# PICZone.net
KiCad netlist of a schematic drawn in Altium Designer
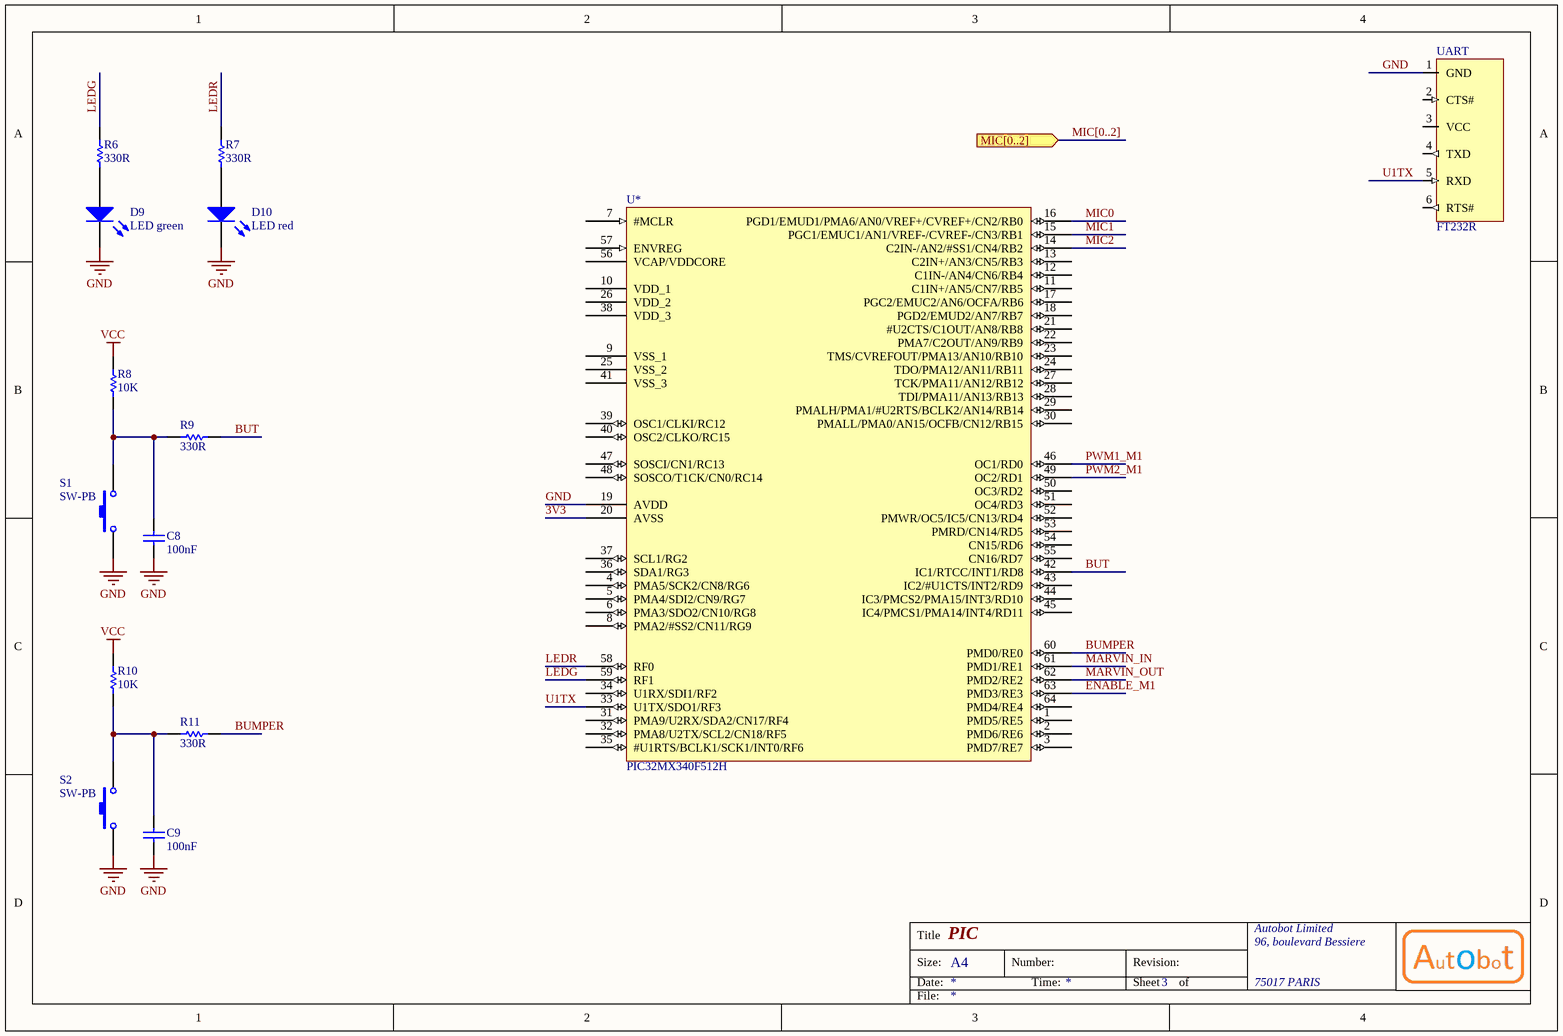
[diagram p0: PICZone.SchDoc]

(export (version "E")
  (design (tool "Eeschema 10.0.6"))
  (components
    (comp (ref "C8")
      (value "100nF")
      (footprint "RAD-0.3")
      (description "Capacitor")
      (fields (field (name "PUBLISHER") "Altium Limited"))
      (libsource (lib "Miscellaneous Devices") (part "Cap"))
    )
    (comp (ref "C9")
      (value "100nF")
      (footprint "RAD-0.3")
      (description "Capacitor")
      (fields (field (name "PUBLISHER") "Altium Limited"))
      (libsource (lib "Miscellaneous Devices") (part "Cap"))
    )
    (comp (ref "D9")
      (value "LED green")
      (footprint "LED-0")
      (description "Typical INFRARED GaAs LED")
      (fields (field (name "PUBLISHER") "Altium Limited"))
      (libsource (lib "Miscellaneous Devices") (part "LED0"))
    )
    (comp (ref "D10")
      (value "LED red")
      (footprint "LED-0")
      (description "Typical INFRARED GaAs LED")
      (fields (field (name "PUBLISHER") "Altium Limited"))
      (libsource (lib "Miscellaneous Devices") (part "LED0"))
    )
    (comp (ref "R6")
      (value "330R")
      (footprint "AXIAL-0.3")
      (description "Resistor")
      (fields (field (name "PUBLISHER") "Altium Limited"))
      (libsource (lib "Miscellaneous Devices") (part "Res1"))
    )
    (comp (ref "R7")
      (value "330R")
      (footprint "AXIAL-0.3")
      (description "Resistor")
      (fields (field (name "PUBLISHER") "Altium Limited"))
      (libsource (lib "Miscellaneous Devices") (part "Res1"))
    )
    (comp (ref "R8")
      (value "10K")
      (footprint "AXIAL-0.3")
      (description "Resistor")
      (fields (field (name "PUBLISHER") "Altium Limited"))
      (libsource (lib "Miscellaneous Devices") (part "Res1"))
    )
    (comp (ref "R9")
      (value "330R")
      (footprint "AXIAL-0.3")
      (description "Resistor")
      (fields (field (name "PUBLISHER") "Altium Limited"))
      (libsource (lib "Miscellaneous Devices") (part "Res1"))
    )
    (comp (ref "R10")
      (value "10K")
      (footprint "AXIAL-0.3")
      (description "Resistor")
      (fields (field (name "PUBLISHER") "Altium Limited"))
      (libsource (lib "Miscellaneous Devices") (part "Res1"))
    )
    (comp (ref "R11")
      (value "330R")
      (footprint "AXIAL-0.3")
      (description "Resistor")
      (fields (field (name "PUBLISHER") "Altium Limited"))
      (libsource (lib "Miscellaneous Devices") (part "Res1"))
    )
    (comp (ref "S1")
      (value "SW-PB")
      (footprint "SPST-2")
      (description "Switch")
      (fields (field (name "PUBLISHER") "Altium Limited"))
      (libsource (lib "Miscellaneous Devices") (part "SW-PB"))
    )
    (comp (ref "S2")
      (value "SW-PB")
      (footprint "SPST-2")
      (description "Switch")
      (fields (field (name "PUBLISHER") "Altium Limited"))
      (libsource (lib "Miscellaneous Devices") (part "SW-PB"))
    )
    (comp (ref "U*") (value "PIC32MX340F512H") (libsource (lib "SCHLIB_Autobot") (part "PIC32MX340F512H")))
    (comp (ref "UART") (value "FT232R") (libsource (lib "SCHLIB_Autobot") (part "FT232R")))
  )
  (nets
    (net (code "1") (name "/3V3") (class "Default")
      (node (ref "U*") (pin "20") (pinfunction "AVSS_20") (pintype "power_in"))
    )
    (net (code "2") (name "/BUMPER") (class "Default")
      (node (ref "R11") (pin "1") (pinfunction "1_1") (pintype "passive"))
      (node (ref "U*") (pin "60") (pinfunction "PMD0/RE0_60") (pintype "bidirectional"))
    )
    (net (code "3") (name "/BUT") (class "Default")
      (node (ref "R9") (pin "1") (pinfunction "1_1") (pintype "passive"))
      (node (ref "U*") (pin "42") (pinfunction "IC1/RTCC/INT1/RD8_42") (pintype "bidirectional"))
    )
    (net (code "4") (name "/ENABLE_M1") (class "Default")
      (node (ref "U*") (pin "63") (pinfunction "PMD3/RE3_63") (pintype "bidirectional"))
    )
    (net (code "5") (name "/LEDG") (class "Default")
      (node (ref "R6") (pin "2") (pinfunction "2_2") (pintype "passive"))
      (node (ref "U*") (pin "59") (pinfunction "RF1_59") (pintype "bidirectional"))
    )
    (net (code "6") (name "/LEDR") (class "Default")
      (node (ref "R7") (pin "2") (pinfunction "2_2") (pintype "passive"))
      (node (ref "U*") (pin "58") (pinfunction "RF0_58") (pintype "bidirectional"))
    )
    (net (code "7") (name "/MARVIN_IN") (class "Default")
      (node (ref "U*") (pin "61") (pinfunction "PMD1/RE1_61") (pintype "bidirectional"))
    )
    (net (code "8") (name "/MARVIN_OUT") (class "Default")
      (node (ref "U*") (pin "62") (pinfunction "PMD2/RE2_62") (pintype "bidirectional"))
    )
    (net (code "9") (name "/MIC0") (class "Default")
      (node (ref "U*") (pin "16") (pinfunction "PGD1/EMUD1/PMA6/AN0/VREF+/CVREF+/CN2/RB0_16") (pintype "bidirectional"))
    )
    (net (code "10") (name "/MIC1") (class "Default")
      (node (ref "U*") (pin "15") (pinfunction "PGC1/EMUC1/AN1/VREF-/CVREF-/CN3/RB1_15") (pintype "bidirectional"))
    )
    (net (code "11") (name "/MIC2") (class "Default")
      (node (ref "U*") (pin "14") (pinfunction "C2IN-/AN2/#SS1/CN4/RB2_14") (pintype "bidirectional"))
    )
    (net (code "13") (name "/PWM1_M1") (class "Default")
      (node (ref "U*") (pin "46") (pinfunction "OC1/RD0_46") (pintype "bidirectional"))
    )
    (net (code "14") (name "/PWM2_M1") (class "Default")
      (node (ref "U*") (pin "49") (pinfunction "OC2/RD1_49") (pintype "bidirectional"))
    )
    (net (code "15") (name "/U1TX") (class "Default")
      (node (ref "U*") (pin "33") (pinfunction "U1TX/SDO1/RF3_33") (pintype "bidirectional"))
      (node (ref "UART") (pin "5") (pinfunction "RXD_5") (pintype "input"))
    )
    (net (code "16") (name "GND") (class "Default")
      (node (ref "C8") (pin "2") (pinfunction "2_2") (pintype "passive"))
      (node (ref "C9") (pin "2") (pinfunction "2_2") (pintype "passive"))
      (node (ref "D10") (pin "2") (pinfunction "K_2") (pintype "passive"))
      (node (ref "D9") (pin "2") (pinfunction "K_2") (pintype "passive"))
      (node (ref "S1") (pin "1") (pinfunction "1_1") (pintype "passive"))
      (node (ref "S2") (pin "1") (pinfunction "1_1") (pintype "passive"))
      (node (ref "U*") (pin "19") (pinfunction "AVDD_19") (pintype "power_in"))
      (node (ref "UART") (pin "1") (pinfunction "GND_1") (pintype "passive"))
    )
    (net (code "17") (name "Net-(C8-Pad1)") (class "Default")
      (node (ref "C8") (pin "1") (pinfunction "1_1") (pintype "passive"))
      (node (ref "R8") (pin "1") (pinfunction "1_1") (pintype "passive"))
      (node (ref "R9") (pin "2") (pinfunction "2_2") (pintype "passive"))
      (node (ref "S1") (pin "2") (pinfunction "2_2") (pintype "passive"))
    )
    (net (code "18") (name "Net-(C9-Pad1)") (class "Default")
      (node (ref "C9") (pin "1") (pinfunction "1_1") (pintype "passive"))
      (node (ref "R10") (pin "1") (pinfunction "1_1") (pintype "passive"))
      (node (ref "R11") (pin "2") (pinfunction "2_2") (pintype "passive"))
      (node (ref "S2") (pin "2") (pinfunction "2_2") (pintype "passive"))
    )
    (net (code "19") (name "Net-(D9-A)") (class "Default")
      (node (ref "D9") (pin "1") (pinfunction "A_1") (pintype "passive"))
      (node (ref "R6") (pin "1") (pinfunction "1_1") (pintype "passive"))
    )
    (net (code "20") (name "Net-(D10-A)") (class "Default")
      (node (ref "D10") (pin "1") (pinfunction "A_1") (pintype "passive"))
      (node (ref "R7") (pin "1") (pinfunction "1_1") (pintype "passive"))
    )
    (net (code "21") (name "VCC") (class "Default")
      (node (ref "R10") (pin "2") (pinfunction "2_2") (pintype "passive"))
      (node (ref "R8") (pin "2") (pinfunction "2_2") (pintype "passive"))
    )
    (net (code "22") (name "unconnected-(U*-#MCLR-Pad7)") (class "Default")
      (node (ref "U*") (pin "7") (pinfunction "#MCLR_7") (pintype "input"))
    )
    (net (code "23") (name "unconnected-(U*-#U1RTS{slash}BCLK1{slash}SCK1{slash}INT0{slash}RF6-Pad35)") (class "Default")
      (node (ref "U*") (pin "35") (pinfunction "#U1RTS/BCLK1/SCK1/INT0/RF6_35") (pintype "bidirectional"))
    )
    (net (code "24") (name "unconnected-(U*-#U2CTS{slash}C1OUT{slash}AN8{slash}RB8-Pad21)") (class "Default")
      (node (ref "U*") (pin "21") (pinfunction "#U2CTS/C1OUT/AN8/RB8_21") (pintype "bidirectional"))
    )
    (net (code "25") (name "unconnected-(U*-C1IN+{slash}AN5{slash}CN7{slash}RB5-Pad11)") (class "Default")
      (node (ref "U*") (pin "11") (pinfunction "C1IN+/AN5/CN7/RB5_11") (pintype "bidirectional"))
    )
    (net (code "26") (name "unconnected-(U*-C1IN-{slash}AN4{slash}CN6{slash}RB4-Pad12)") (class "Default")
      (node (ref "U*") (pin "12") (pinfunction "C1IN-/AN4/CN6/RB4_12") (pintype "bidirectional"))
    )
    (net (code "27") (name "unconnected-(U*-C2IN+{slash}AN3{slash}CN5{slash}RB3-Pad13)") (class "Default")
      (node (ref "U*") (pin "13") (pinfunction "C2IN+/AN3/CN5/RB3_13") (pintype "bidirectional"))
    )
    (net (code "28") (name "unconnected-(U*-CN15{slash}RD6-Pad54)") (class "Default")
      (node (ref "U*") (pin "54") (pinfunction "CN15/RD6_54") (pintype "bidirectional"))
    )
    (net (code "29") (name "unconnected-(U*-CN16{slash}RD7-Pad55)") (class "Default")
      (node (ref "U*") (pin "55") (pinfunction "CN16/RD7_55") (pintype "bidirectional"))
    )
    (net (code "30") (name "unconnected-(U*-ENVREG-Pad57)") (class "Default")
      (node (ref "U*") (pin "57") (pinfunction "ENVREG_57") (pintype "input"))
    )
    (net (code "31") (name "unconnected-(U*-IC2{slash}#U1CTS{slash}INT2{slash}RD9-Pad43)") (class "Default")
      (node (ref "U*") (pin "43") (pinfunction "IC2/#U1CTS/INT2/RD9_43") (pintype "bidirectional"))
    )
    (net (code "32") (name "unconnected-(U*-IC3{slash}PMCS2{slash}PMA15{slash}INT3{slash}RD10-Pad44)") (class "Default")
      (node (ref "U*") (pin "44") (pinfunction "IC3/PMCS2/PMA15/INT3/RD10_44") (pintype "bidirectional"))
    )
    (net (code "33") (name "unconnected-(U*-IC4{slash}PMCS1{slash}PMA14{slash}INT4{slash}RD11-Pad45)") (class "Default")
      (node (ref "U*") (pin "45") (pinfunction "IC4/PMCS1/PMA14/INT4/RD11_45") (pintype "bidirectional"))
    )
    (net (code "34") (name "unconnected-(U*-OC3{slash}RD2-Pad50)") (class "Default")
      (node (ref "U*") (pin "50") (pinfunction "OC3/RD2_50") (pintype "bidirectional"))
    )
    (net (code "35") (name "unconnected-(U*-OC4{slash}RD3-Pad51)") (class "Default")
      (node (ref "U*") (pin "51") (pinfunction "OC4/RD3_51") (pintype "bidirectional"))
    )
    (net (code "36") (name "unconnected-(U*-OSC1{slash}CLKI{slash}RC12-Pad39)") (class "Default")
      (node (ref "U*") (pin "39") (pinfunction "OSC1/CLKI/RC12_39") (pintype "bidirectional"))
    )
    (net (code "37") (name "unconnected-(U*-OSC2{slash}CLKO{slash}RC15-Pad40)") (class "Default")
      (node (ref "U*") (pin "40") (pinfunction "OSC2/CLKO/RC15_40") (pintype "bidirectional"))
    )
    (net (code "38") (name "unconnected-(U*-PGC2{slash}EMUC2{slash}AN6{slash}OCFA{slash}RB6-Pad17)") (class "Default")
      (node (ref "U*") (pin "17") (pinfunction "PGC2/EMUC2/AN6/OCFA/RB6_17") (pintype "bidirectional"))
    )
    (net (code "39") (name "unconnected-(U*-PGD2{slash}EMUD2{slash}AN7{slash}RB7-Pad18)") (class "Default")
      (node (ref "U*") (pin "18") (pinfunction "PGD2/EMUD2/AN7/RB7_18") (pintype "bidirectional"))
    )
    (net (code "40") (name "unconnected-(U*-PMA2{slash}#SS2{slash}CN11{slash}RG9-Pad8)") (class "Default")
      (node (ref "U*") (pin "8") (pinfunction "PMA2/#SS2/CN11/RG9_8") (pintype "bidirectional"))
    )
    (net (code "41") (name "unconnected-(U*-PMA3{slash}SDO2{slash}CN10{slash}RG8-Pad6)") (class "Default")
      (node (ref "U*") (pin "6") (pinfunction "PMA3/SDO2/CN10/RG8_6") (pintype "bidirectional"))
    )
    (net (code "42") (name "unconnected-(U*-PMA4{slash}SDI2{slash}CN9{slash}RG7-Pad5)") (class "Default")
      (node (ref "U*") (pin "5") (pinfunction "PMA4/SDI2/CN9/RG7_5") (pintype "bidirectional"))
    )
    (net (code "43") (name "unconnected-(U*-PMA5{slash}SCK2{slash}CN8{slash}RG6-Pad4)") (class "Default")
      (node (ref "U*") (pin "4") (pinfunction "PMA5/SCK2/CN8/RG6_4") (pintype "bidirectional"))
    )
    (net (code "44") (name "unconnected-(U*-PMA7{slash}C2OUT{slash}AN9{slash}RB9-Pad22)") (class "Default")
      (node (ref "U*") (pin "22") (pinfunction "PMA7/C2OUT/AN9/RB9_22") (pintype "bidirectional"))
    )
    (net (code "45") (name "unconnected-(U*-PMA8{slash}U2TX{slash}SCL2{slash}CN18{slash}RF5-Pad32)") (class "Default")
      (node (ref "U*") (pin "32") (pinfunction "PMA8/U2TX/SCL2/CN18/RF5_32") (pintype "bidirectional"))
    )
    (net (code "46") (name "unconnected-(U*-PMA9{slash}U2RX{slash}SDA2{slash}CN17{slash}RF4-Pad31)") (class "Default")
      (node (ref "U*") (pin "31") (pinfunction "PMA9/U2RX/SDA2/CN17/RF4_31") (pintype "bidirectional"))
    )
    (net (code "47") (name "unconnected-(U*-PMALH{slash}PMA1{slash}#U2RTS{slash}BCLK2{slash}AN14{slash}RB14-Pad29)") (class "Default")
      (node (ref "U*") (pin "29") (pinfunction "PMALH/PMA1/#U2RTS/BCLK2/AN14/RB14_29") (pintype "bidirectional"))
    )
    (net (code "48") (name "unconnected-(U*-PMALL{slash}PMA0{slash}AN15{slash}OCFB{slash}CN12{slash}RB15-Pad30)") (class "Default")
      (node (ref "U*") (pin "30") (pinfunction "PMALL/PMA0/AN15/OCFB/CN12/RB15_30") (pintype "bidirectional"))
    )
    (net (code "49") (name "unconnected-(U*-PMD4{slash}RE4-Pad64)") (class "Default")
      (node (ref "U*") (pin "64") (pinfunction "PMD4/RE4_64") (pintype "bidirectional"))
    )
    (net (code "50") (name "unconnected-(U*-PMD5{slash}RE5-Pad1)") (class "Default")
      (node (ref "U*") (pin "1") (pinfunction "PMD5/RE5_1") (pintype "bidirectional"))
    )
    (net (code "51") (name "unconnected-(U*-PMD6{slash}RE6-Pad2)") (class "Default")
      (node (ref "U*") (pin "2") (pinfunction "PMD6/RE6_2") (pintype "bidirectional"))
    )
    (net (code "52") (name "unconnected-(U*-PMD7{slash}RE7-Pad3)") (class "Default")
      (node (ref "U*") (pin "3") (pinfunction "PMD7/RE7_3") (pintype "bidirectional"))
    )
    (net (code "53") (name "unconnected-(U*-PMRD{slash}CN14{slash}RD5-Pad53)") (class "Default")
      (node (ref "U*") (pin "53") (pinfunction "PMRD/CN14/RD5_53") (pintype "bidirectional"))
    )
    (net (code "54") (name "unconnected-(U*-PMWR{slash}OC5{slash}IC5{slash}CN13{slash}RD4-Pad52)") (class "Default")
      (node (ref "U*") (pin "52") (pinfunction "PMWR/OC5/IC5/CN13/RD4_52") (pintype "bidirectional"))
    )
    (net (code "55") (name "unconnected-(U*-SCL1{slash}RG2-Pad37)") (class "Default")
      (node (ref "U*") (pin "37") (pinfunction "SCL1/RG2_37") (pintype "bidirectional"))
    )
    (net (code "56") (name "unconnected-(U*-SDA1{slash}RG3-Pad36)") (class "Default")
      (node (ref "U*") (pin "36") (pinfunction "SDA1/RG3_36") (pintype "bidirectional"))
    )
    (net (code "57") (name "unconnected-(U*-SOSCI{slash}CN1{slash}RC13-Pad47)") (class "Default")
      (node (ref "U*") (pin "47") (pinfunction "SOSCI/CN1/RC13_47") (pintype "bidirectional"))
    )
    (net (code "58") (name "unconnected-(U*-SOSCO{slash}T1CK{slash}CN0{slash}RC14-Pad48)") (class "Default")
      (node (ref "U*") (pin "48") (pinfunction "SOSCO/T1CK/CN0/RC14_48") (pintype "bidirectional"))
    )
    (net (code "59") (name "unconnected-(U*-TCK{slash}PMA11{slash}AN12{slash}RB12-Pad27)") (class "Default")
      (node (ref "U*") (pin "27") (pinfunction "TCK/PMA11/AN12/RB12_27") (pintype "bidirectional"))
    )
    (net (code "60") (name "unconnected-(U*-TDI{slash}PMA11{slash}AN13{slash}RB13-Pad28)") (class "Default")
      (node (ref "U*") (pin "28") (pinfunction "TDI/PMA11/AN13/RB13_28") (pintype "bidirectional"))
    )
    (net (code "61") (name "unconnected-(U*-TDO{slash}PMA12{slash}AN11{slash}RB11-Pad24)") (class "Default")
      (node (ref "U*") (pin "24") (pinfunction "TDO/PMA12/AN11/RB11_24") (pintype "bidirectional"))
    )
    (net (code "62") (name "unconnected-(U*-TMS{slash}CVREFOUT{slash}PMA13{slash}AN10{slash}RB10-Pad23)") (class "Default")
      (node (ref "U*") (pin "23") (pinfunction "TMS/CVREFOUT/PMA13/AN10/RB10_23") (pintype "bidirectional"))
    )
    (net (code "63") (name "unconnected-(U*-U1RX{slash}SDI1{slash}RF2-Pad34)") (class "Default")
      (node (ref "U*") (pin "34") (pinfunction "U1RX/SDI1/RF2_34") (pintype "bidirectional"))
    )
    (net (code "64") (name "unconnected-(U*-VCAP{slash}VDDCORE-Pad56)") (class "Default")
      (node (ref "U*") (pin "56") (pinfunction "VCAP/VDDCORE_56") (pintype "power_in"))
    )
    (net (code "65") (name "unconnected-(U*-VDD_1-Pad10)") (class "Default")
      (node (ref "U*") (pin "10") (pinfunction "VDD_1_10") (pintype "power_in"))
    )
    (net (code "66") (name "unconnected-(U*-VDD_2-Pad26)") (class "Default")
      (node (ref "U*") (pin "26") (pinfunction "VDD_2_26") (pintype "power_in"))
    )
    (net (code "67") (name "unconnected-(U*-VDD_3-Pad38)") (class "Default")
      (node (ref "U*") (pin "38") (pinfunction "VDD_3_38") (pintype "power_in"))
    )
    (net (code "68") (name "unconnected-(U*-VSS_1-Pad9)") (class "Default")
      (node (ref "U*") (pin "9") (pinfunction "VSS_1_9") (pintype "power_in"))
    )
    (net (code "69") (name "unconnected-(U*-VSS_2-Pad25)") (class "Default")
      (node (ref "U*") (pin "25") (pinfunction "VSS_2_25") (pintype "power_in"))
    )
    (net (code "70") (name "unconnected-(U*-VSS_3-Pad41)") (class "Default")
      (node (ref "U*") (pin "41") (pinfunction "VSS_3_41") (pintype "power_in"))
    )
    (net (code "71") (name "unconnected-(UART-CTS#-Pad2)") (class "Default")
      (node (ref "UART") (pin "2") (pinfunction "CTS#_2") (pintype "input"))
    )
    (net (code "72") (name "unconnected-(UART-RTS#-Pad6)") (class "Default")
      (node (ref "UART") (pin "6") (pinfunction "RTS#_6") (pintype "output"))
    )
    (net (code "73") (name "unconnected-(UART-TXD-Pad4)") (class "Default")
      (node (ref "UART") (pin "4") (pinfunction "TXD_4") (pintype "output"))
    )
    (net (code "74") (name "unconnected-(UART-VCC-Pad3)") (class "Default")
      (node (ref "UART") (pin "3") (pinfunction "VCC_3") (pintype "power_in"))
    )
  )
)
